# FunskjonsBlokkskjema.net
KiCad netlist of a schematic drawn in Altium Designer
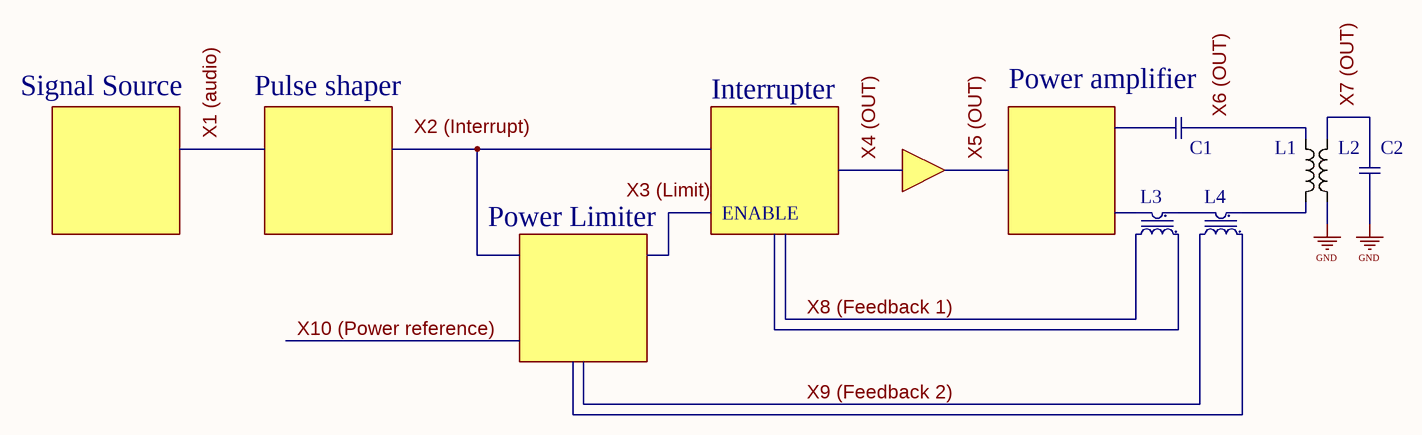
[diagram p0: FunskjonsBlokkskjema.SchDoc]

(export (version "E")
  (design (tool "Eeschema 10.0.6"))
  (components
    (comp (ref "C1")
      (value "100nF")
      (footprint "CAPC0603(1608)55_N")
      (description "X7R 50V 5%")
      (libsource (lib "OVLib") (part "CAP"))
    )
    (comp (ref "C2")
      (value "100nF")
      (footprint "CAPC0603(1608)55_N")
      (description "X7R 50V 5%")
      (libsource (lib "OVLib") (part "CAP"))
    )
    (comp (ref "L1")
      (value "SMD spoler")
      (footprint "INDP3225X20N")
      (description "SMD inductors og tomme SMD bokser")
      (libsource (lib "OVLib") (part "IND_GENERIC"))
    )
    (comp (ref "L2")
      (value "SMD spoler")
      (footprint "INDP3225X20N")
      (description "SMD inductors og tomme SMD bokser")
      (libsource (lib "OVLib") (part "IND_GENERIC"))
    )
    (comp (ref "L3")
      (value "CurrentSenseTransformer")
      (libsource (lib "OVLib") (part "Current_sensing_transformer"))
    )
    (comp (ref "L4")
      (value "CurrentSenseTransformer")
      (libsource (lib "OVLib") (part "Current_sensing_transformer"))
    )
  )
  (nets
    (net (code "8") (name "/X8 (Feedback 1)") (class "Default")
      (node (ref "L3") (pin "3") (pinfunction "3_3") (pintype "passive"))
    )
    (net (code "9") (name "/X9 (Feedback 2)") (class "Default")
      (node (ref "L4") (pin "3") (pinfunction "3_3") (pintype "passive"))
    )
    (net (code "11") (name "GND") (class "Default")
      (node (ref "C2") (pin "2") (pinfunction "2_2") (pintype "passive"))
      (node (ref "L2") (pin "1") (pinfunction "1_1") (pintype "passive"))
    )
    (net (code "12") (name "Net-(C1-Pad1)") (class "Default")
      (node (ref "C1") (pin "1") (pinfunction "1_1") (pintype "passive"))
      (node (ref "L1") (pin "1") (pinfunction "1_1") (pintype "passive"))
    )
    (net (code "13") (name "Net-(C2-Pad1)") (class "Default")
      (node (ref "C2") (pin "1") (pinfunction "1_1") (pintype "passive"))
      (node (ref "L2") (pin "2") (pinfunction "2_2") (pintype "passive"))
    )
    (net (code "14") (name "Net-(L1-Pad2)") (class "Default")
      (node (ref "L1") (pin "2") (pinfunction "2_2") (pintype "passive"))
      (node (ref "L4") (pin "2") (pinfunction "2_2") (pintype "passive"))
    )
    (net (code "15") (name "Net-(L3-Pad2)") (class "Default")
      (node (ref "L3") (pin "2") (pinfunction "2_2") (pintype "passive"))
      (node (ref "L4") (pin "1") (pinfunction "1_1") (pintype "passive"))
    )
    (net (code "16") (name "unconnected-(C1-Pad2)") (class "Default")
      (node (ref "C1") (pin "2") (pinfunction "2_2") (pintype "passive"))
    )
    (net (code "17") (name "unconnected-(L3-Pad1)") (class "Default")
      (node (ref "L3") (pin "1") (pinfunction "1_1") (pintype "passive"))
    )
    (net (code "18") (name "unconnected-(L3-Pad4)") (class "Default")
      (node (ref "L3") (pin "4") (pinfunction "4_4") (pintype "passive"))
    )
    (net (code "19") (name "unconnected-(L4-Pad4)") (class "Default")
      (node (ref "L4") (pin "4") (pinfunction "4_4") (pintype "passive"))
    )
  )
)
